# Scart.net
KiCad netlist of a schematic drawn in EAGLE
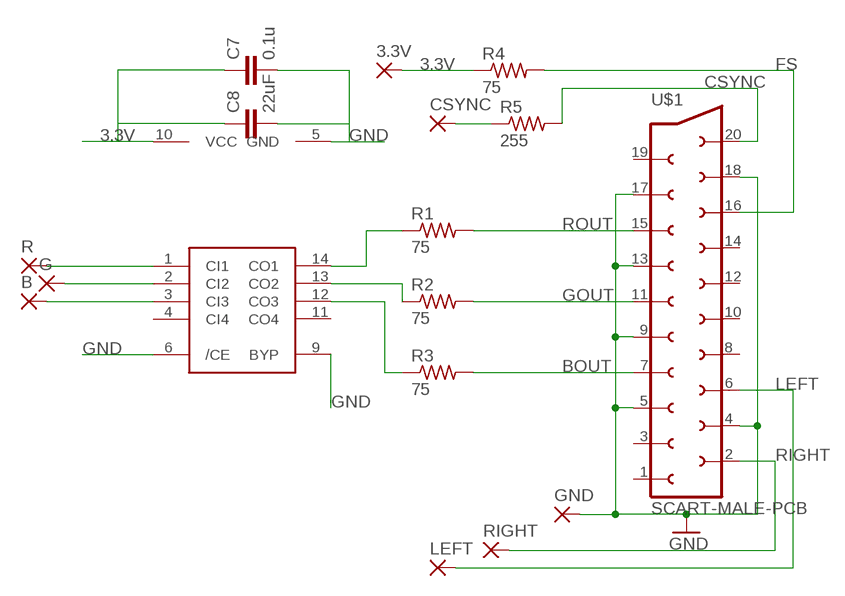
[diagram p0: schematic, sheet 1]

(export (version "E")
  (design (tool "Eeschema 10.0.6"))
  (components
    (comp (ref "3.3V")
      (value "WIREPADSMD1,27-254")
      (footprint "eagle-import:SMD1,27-2,54")
      (libsource (lib "eagle-import") (part "WIREPADSMD1,27-254"))
    )
    (comp (ref "B")
      (value "WIREPADSMD1,27-254")
      (footprint "eagle-import:SMD1,27-2,54")
      (libsource (lib "eagle-import") (part "WIREPADSMD1,27-254"))
    )
    (comp (ref "C7")
      (value "0.1u")
      (footprint "eagle-import:C0805K")
      (libsource (lib "eagle-import") (part "C-EUC0805K"))
    )
    (comp (ref "C8")
      (value "22uF")
      (footprint "eagle-import:C0805K")
      (libsource (lib "eagle-import") (part "C-EUC0805K"))
    )
    (comp (ref "CSYNC")
      (value "WIREPADSMD1,27-254")
      (footprint "eagle-import:SMD1,27-2,54")
      (libsource (lib "eagle-import") (part "WIREPADSMD1,27-254"))
    )
    (comp (ref "G")
      (value "WIREPADSMD1,27-254")
      (footprint "eagle-import:SMD1,27-2,54")
      (libsource (lib "eagle-import") (part "WIREPADSMD1,27-254"))
    )
    (comp (ref "GND")
      (value "WIREPADSMD1,27-254")
      (footprint "eagle-import:SMD1,27-2,54")
      (libsource (lib "eagle-import") (part "WIREPADSMD1,27-254"))
    )
    (comp (ref "LEFT")
      (value "WIREPADSMD1,27-254")
      (footprint "eagle-import:SMD1,27-2,54")
      (libsource (lib "eagle-import") (part "WIREPADSMD1,27-254"))
    )
    (comp (ref "R")
      (value "WIREPADSMD1,27-254")
      (footprint "eagle-import:SMD1,27-2,54")
      (libsource (lib "eagle-import") (part "WIREPADSMD1,27-254"))
    )
    (comp (ref "R1")
      (value "75")
      (footprint "eagle-import:R0805")
      (libsource (lib "eagle-import") (part "R-US_R0805"))
    )
    (comp (ref "R2")
      (value "75")
      (footprint "eagle-import:R0805")
      (libsource (lib "eagle-import") (part "R-US_R0805"))
    )
    (comp (ref "R3")
      (value "75")
      (footprint "eagle-import:R0805")
      (libsource (lib "eagle-import") (part "R-US_R0805"))
    )
    (comp (ref "R4")
      (value "75")
      (footprint "eagle-import:R0805")
      (libsource (lib "eagle-import") (part "R-US_R0805"))
    )
    (comp (ref "R5")
      (value "255")
      (footprint "eagle-import:R0805")
      (libsource (lib "eagle-import") (part "R-US_R0805"))
    )
    (comp (ref "RIGHT")
      (value "WIREPADSMD1,27-254")
      (footprint "eagle-import:SMD1,27-2,54")
      (libsource (lib "eagle-import") (part "WIREPADSMD1,27-254"))
    )
    (comp (ref "U$1")
      (value "SCART-MALE-PCB")
      (footprint "eagle-import:SCART-PCB")
      (libsource (lib "eagle-import") (part "SCART-MALE-PCB"))
    )
    (comp (ref "U$2")
      (value "THS7374")
      (footprint "eagle-import:THS7374")
      (libsource (lib "eagle-import") (part "THS7374"))
    )
  )
  (nets
    (net (code "1") (name "/3.3V") (class "Default")
      (node (ref "3.3V") (pin "1") (pinfunction "P_1") (pintype "passive"))
      (node (ref "C7") (pin "1") (pinfunction "1_1") (pintype "passive"))
      (node (ref "C8") (pin "1") (pinfunction "1_1") (pintype "passive"))
      (node (ref "R4") (pin "1") (pinfunction "1_1") (pintype "passive"))
      (node (ref "U$2") (pin "10") (pinfunction "VCC_10") (pintype "bidirectional"))
    )
    (net (code "2") (name "/BOUT") (class "Default")
      (node (ref "R3") (pin "2") (pinfunction "2_2") (pintype "passive"))
      (node (ref "U$1") (pin "7") (pinfunction "7_7") (pintype "passive"))
    )
    (net (code "3") (name "/CSYNC") (class "Default")
      (node (ref "R5") (pin "2") (pinfunction "2_2") (pintype "passive"))
      (node (ref "U$1") (pin "20") (pinfunction "20_20") (pintype "passive"))
    )
    (net (code "4") (name "/FS") (class "Default")
      (node (ref "R4") (pin "2") (pinfunction "2_2") (pintype "passive"))
      (node (ref "U$1") (pin "16") (pinfunction "16_16") (pintype "passive"))
    )
    (net (code "5") (name "/GOUT") (class "Default")
      (node (ref "R2") (pin "2") (pinfunction "2_2") (pintype "passive"))
      (node (ref "U$1") (pin "11") (pinfunction "11_11") (pintype "passive"))
    )
    (net (code "6") (name "/LEFT") (class "Default")
      (node (ref "LEFT") (pin "1") (pinfunction "P_1") (pintype "passive"))
      (node (ref "U$1") (pin "6") (pinfunction "6_6") (pintype "passive"))
    )
    (net (code "7") (name "/RIGHT") (class "Default")
      (node (ref "RIGHT") (pin "1") (pinfunction "P_1") (pintype "passive"))
      (node (ref "U$1") (pin "2") (pinfunction "2_2") (pintype "passive"))
    )
    (net (code "8") (name "/ROUT") (class "Default")
      (node (ref "R1") (pin "2") (pinfunction "2_2") (pintype "passive"))
      (node (ref "U$1") (pin "15") (pinfunction "15_15") (pintype "passive"))
    )
    (net (code "9") (name "GND") (class "Default")
      (node (ref "C7") (pin "2") (pinfunction "2_2") (pintype "passive"))
      (node (ref "C8") (pin "2") (pinfunction "2_2") (pintype "passive"))
      (node (ref "GND") (pin "1") (pinfunction "P_1") (pintype "passive"))
      (node (ref "U$1") (pin "13") (pinfunction "13_13") (pintype "passive"))
      (node (ref "U$1") (pin "17") (pinfunction "17_17") (pintype "passive"))
      (node (ref "U$1") (pin "18") (pinfunction "18_18") (pintype "passive"))
      (node (ref "U$1") (pin "4") (pinfunction "4_4") (pintype "passive"))
      (node (ref "U$1") (pin "5") (pinfunction "5_5") (pintype "passive"))
      (node (ref "U$1") (pin "9") (pinfunction "9_9") (pintype "passive"))
      (node (ref "U$2") (pin "5") (pinfunction "GND_5") (pintype "bidirectional"))
      (node (ref "U$2") (pin "6") (pinfunction "/CE_6") (pintype "bidirectional"))
      (node (ref "U$2") (pin "9") (pinfunction "BYP_9") (pintype "bidirectional"))
    )
    (net (code "10") (name "Net-(B-P)") (class "Default")
      (node (ref "B") (pin "1") (pinfunction "P_1") (pintype "passive"))
      (node (ref "U$2") (pin "3") (pinfunction "CI3_3") (pintype "bidirectional"))
    )
    (net (code "11") (name "Net-(CSYNC-P)") (class "Default")
      (node (ref "CSYNC") (pin "1") (pinfunction "P_1") (pintype "passive"))
      (node (ref "R5") (pin "1") (pinfunction "1_1") (pintype "passive"))
    )
    (net (code "12") (name "Net-(G-P)") (class "Default")
      (node (ref "G") (pin "1") (pinfunction "P_1") (pintype "passive"))
      (node (ref "U$2") (pin "2") (pinfunction "CI2_2") (pintype "bidirectional"))
    )
    (net (code "13") (name "Net-(R-P)") (class "Default")
      (node (ref "R") (pin "1") (pinfunction "P_1") (pintype "passive"))
      (node (ref "U$2") (pin "1") (pinfunction "CI1_1") (pintype "bidirectional"))
    )
    (net (code "14") (name "Net-(U$2A-CO1)") (class "Default")
      (node (ref "R1") (pin "1") (pinfunction "1_1") (pintype "passive"))
      (node (ref "U$2") (pin "14") (pinfunction "CO1_14") (pintype "bidirectional"))
    )
    (net (code "15") (name "Net-(U$2A-CO2)") (class "Default")
      (node (ref "R2") (pin "1") (pinfunction "1_1") (pintype "passive"))
      (node (ref "U$2") (pin "13") (pinfunction "CO2_13") (pintype "bidirectional"))
    )
    (net (code "16") (name "Net-(U$2A-CO3)") (class "Default")
      (node (ref "R3") (pin "1") (pinfunction "1_1") (pintype "passive"))
      (node (ref "U$2") (pin "12") (pinfunction "CO3_12") (pintype "bidirectional"))
    )
    (net (code "17") (name "unconnected-(U$1-Pad1)") (class "Default")
      (node (ref "U$1") (pin "1") (pinfunction "1_1") (pintype "passive"))
    )
    (net (code "18") (name "unconnected-(U$1-Pad3)") (class "Default")
      (node (ref "U$1") (pin "3") (pinfunction "3_3") (pintype "passive"))
    )
    (net (code "19") (name "unconnected-(U$1-Pad8)") (class "Default")
      (node (ref "U$1") (pin "8") (pinfunction "8_8") (pintype "passive"))
    )
    (net (code "20") (name "unconnected-(U$1-Pad10)") (class "Default")
      (node (ref "U$1") (pin "10") (pinfunction "10_10") (pintype "passive"))
    )
    (net (code "21") (name "unconnected-(U$1-Pad12)") (class "Default")
      (node (ref "U$1") (pin "12") (pinfunction "12_12") (pintype "passive"))
    )
    (net (code "22") (name "unconnected-(U$1-Pad14)") (class "Default")
      (node (ref "U$1") (pin "14") (pinfunction "14_14") (pintype "passive"))
    )
    (net (code "23") (name "unconnected-(U$1-Pad19)") (class "Default")
      (node (ref "U$1") (pin "19") (pinfunction "19_19") (pintype "passive"))
    )
    (net (code "24") (name "unconnected-(U$2A-CI4-Pad4)") (class "Default")
      (node (ref "U$2") (pin "4") (pinfunction "CI4_4") (pintype "bidirectional"))
    )
    (net (code "25") (name "unconnected-(U$2A-CO4-Pad11)") (class "Default")
      (node (ref "U$2") (pin "11") (pinfunction "CO4_11") (pintype "bidirectional"))
    )
  )
)
